# Sheet_1_2020-10-02_16-46-16.net
KiCad netlist of a schematic drawn in Altium Designer
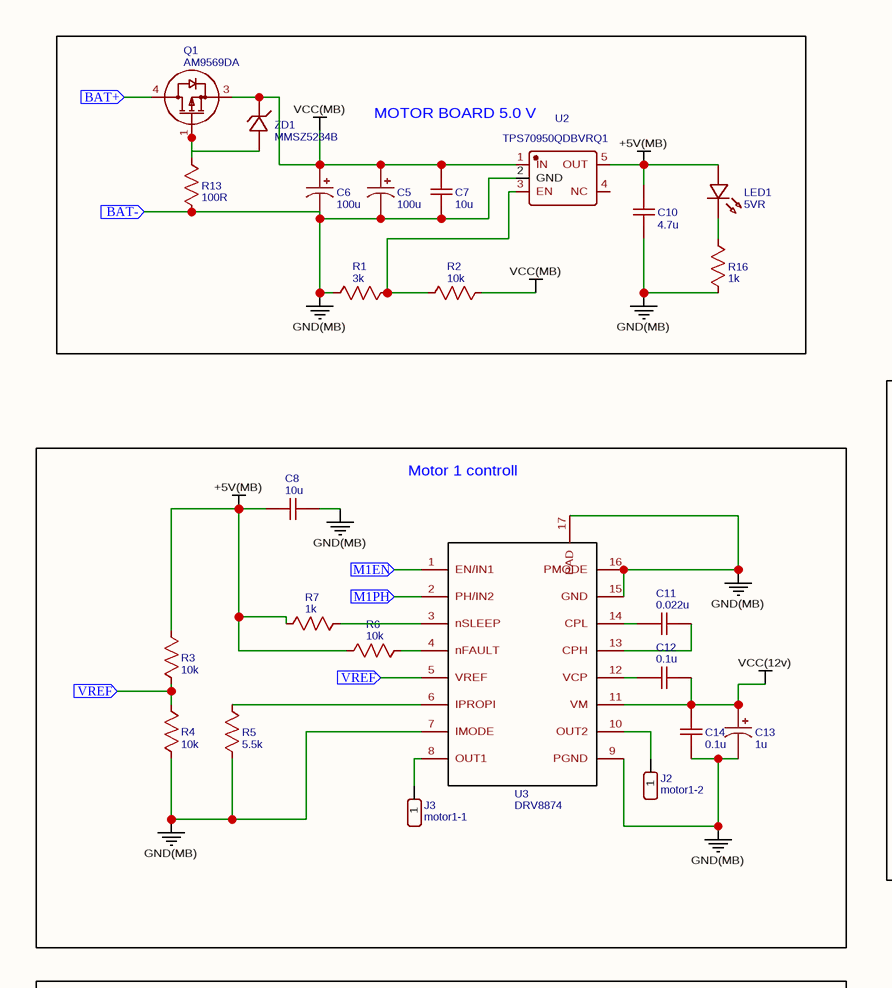
[diagram p0: Sheet_1_2020-10-02_16-46-16.schdoc, top left]
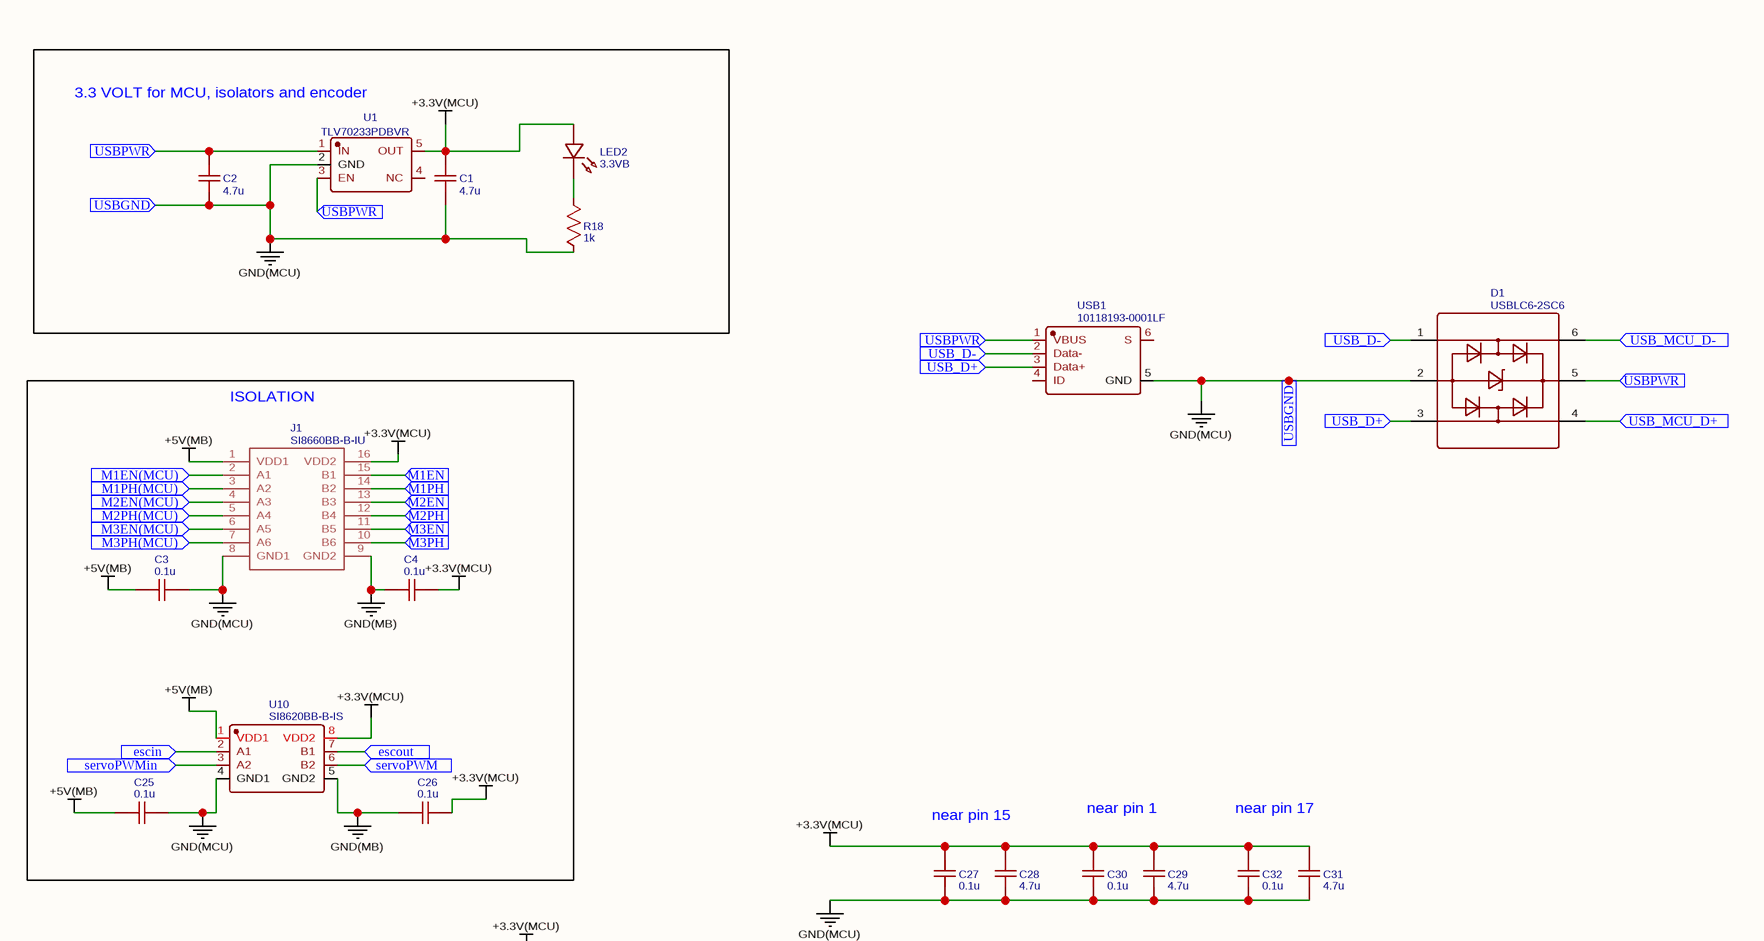
[diagram p1: Sheet_1_2020-10-02_16-46-16.schdoc, top right]
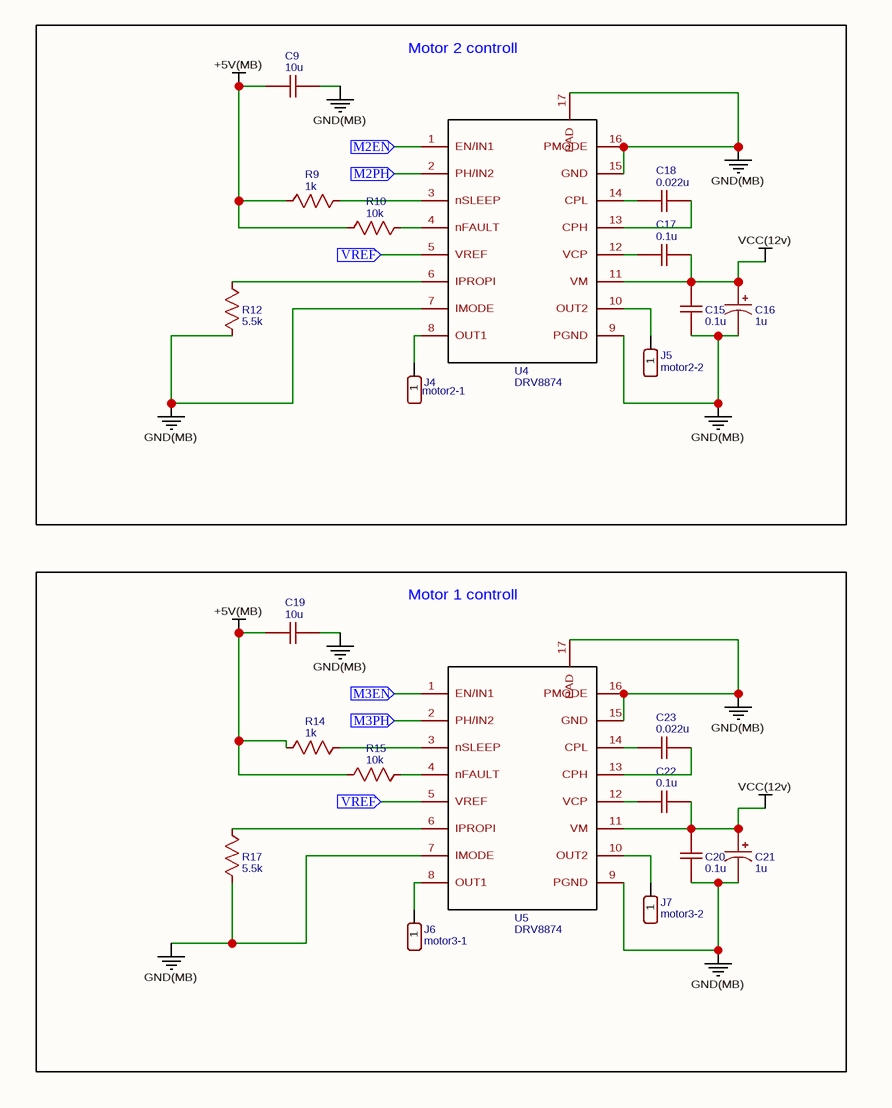
[diagram p2: Sheet_1_2020-10-02_16-46-16.schdoc, bottom left]
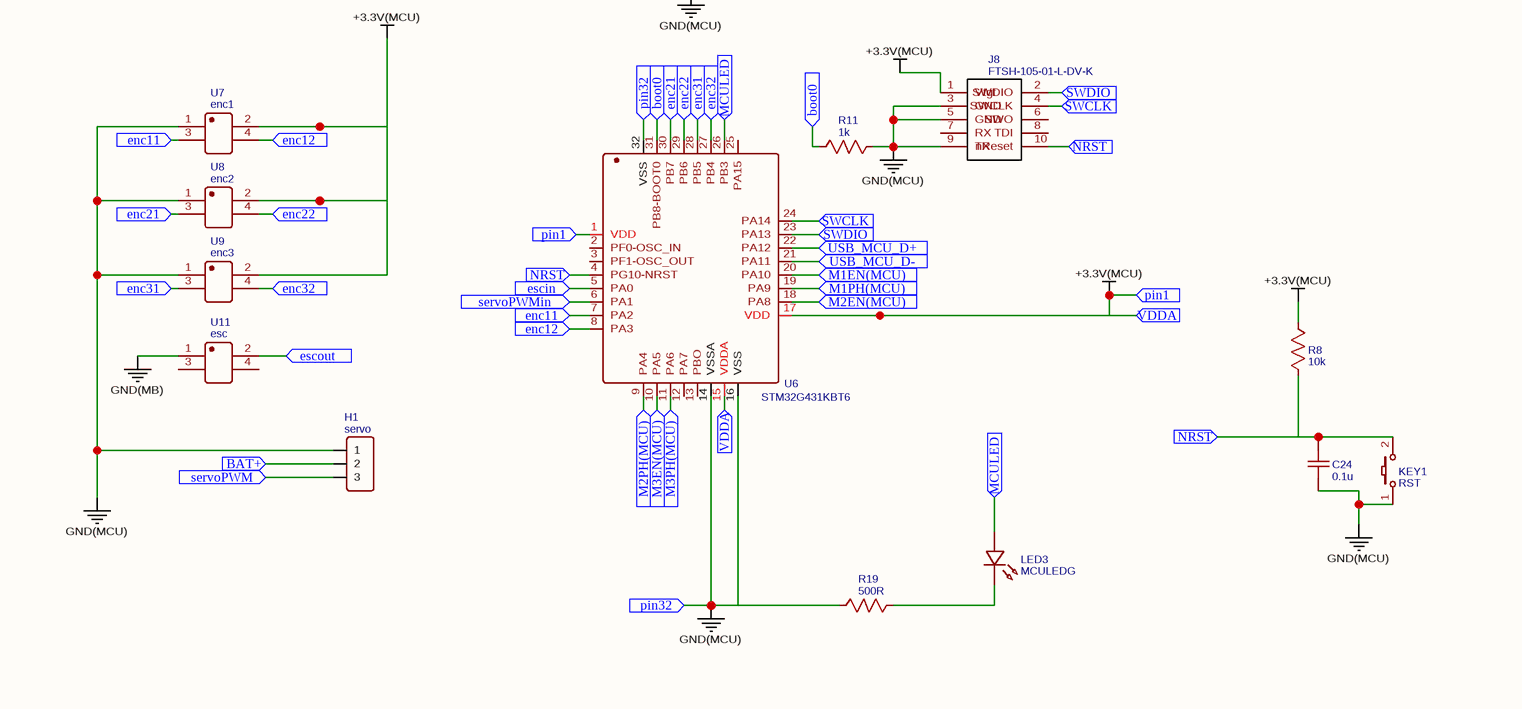
[diagram p3: Sheet_1_2020-10-02_16-46-16.schdoc, bottom right]

(export (version "E")
  (design (tool "Eeschema 10.0.6"))
  (components
    (comp (ref "C1")
      (value "4.7u")
      (fields (field (name "CONTRIBUTOR") "LCEDA_Lib"))
      (libsource (lib "altium-import") (part "root_1_4.7u_"))
    )
    (comp (ref "C2")
      (value "4.7u")
      (fields (field (name "CONTRIBUTOR") "LCEDA_Lib"))
      (libsource (lib "altium-import") (part "root_1_4.7u_"))
    )
    (comp (ref "C3")
      (value "0.1u")
      (fields (field (name "CONTRIBUTOR") "LCEDA_Lib"))
      (libsource (lib "altium-import") (part "root_2_0.1u_"))
    )
    (comp (ref "C4")
      (value "0.1u")
      (fields (field (name "CONTRIBUTOR") "LCEDA_Lib"))
      (libsource (lib "altium-import") (part "root_2_0.1u_"))
    )
    (comp (ref "C5")
      (value "100u")
      (fields (field (name "CONTRIBUTOR") "LCEDA_Lib"))
      (libsource (lib "altium-import") (part "root_3_100u_"))
    )
    (comp (ref "C6")
      (value "100u")
      (fields (field (name "CONTRIBUTOR") "LCEDA_Lib"))
      (libsource (lib "altium-import") (part "root_3_100u_"))
    )
    (comp (ref "C7")
      (value "10u")
      (fields (field (name "CONTRIBUTOR") "LCEDA_Lib"))
      (libsource (lib "altium-import") (part "root_1_10u_"))
    )
    (comp (ref "C8")
      (value "10u")
      (fields (field (name "CONTRIBUTOR") "LCEDA_Lib"))
      (libsource (lib "altium-import") (part "root_0_10u_"))
    )
    (comp (ref "C9")
      (value "10u")
      (fields (field (name "CONTRIBUTOR") "LCEDA_Lib"))
      (libsource (lib "altium-import") (part "root_0_10u_"))
    )
    (comp (ref "C10")
      (value "4.7u")
      (fields (field (name "CONTRIBUTOR") "LCEDA_Lib"))
      (libsource (lib "altium-import") (part "root_1_4.7u_"))
    )
    (comp (ref "C11")
      (value "0.022u")
      (fields (field (name "CONTRIBUTOR") "LCEDA_Lib"))
      (libsource (lib "altium-import") (part "root_0_0.022u_"))
    )
    (comp (ref "C12")
      (value "0.1u")
      (fields (field (name "CONTRIBUTOR") "LCEDA_Lib"))
      (libsource (lib "altium-import") (part "root_0_0.1u_"))
    )
    (comp (ref "C13")
      (value "1u")
      (fields (field (name "CONTRIBUTOR") "LCEDA_Lib"))
      (libsource (lib "altium-import") (part "root_3_1u_"))
    )
    (comp (ref "C14")
      (value "0.1u")
      (fields (field (name "CONTRIBUTOR") "LCEDA_Lib"))
      (libsource (lib "altium-import") (part "root_1_0.1u_"))
    )
    (comp (ref "C15")
      (value "0.1u")
      (fields (field (name "CONTRIBUTOR") "LCEDA_Lib"))
      (libsource (lib "altium-import") (part "root_1_0.1u_"))
    )
    (comp (ref "C16")
      (value "1u")
      (fields (field (name "CONTRIBUTOR") "LCEDA_Lib"))
      (libsource (lib "altium-import") (part "root_3_1u_"))
    )
    (comp (ref "C17")
      (value "0.1u")
      (fields (field (name "CONTRIBUTOR") "LCEDA_Lib"))
      (libsource (lib "altium-import") (part "root_0_0.1u_"))
    )
    (comp (ref "C18")
      (value "0.022u")
      (fields (field (name "CONTRIBUTOR") "LCEDA_Lib"))
      (libsource (lib "altium-import") (part "root_0_0.022u_"))
    )
    (comp (ref "C19")
      (value "10u")
      (fields (field (name "CONTRIBUTOR") "LCEDA_Lib"))
      (libsource (lib "altium-import") (part "root_0_10u_"))
    )
    (comp (ref "C20")
      (value "0.1u")
      (fields (field (name "CONTRIBUTOR") "LCEDA_Lib"))
      (libsource (lib "altium-import") (part "root_1_0.1u_"))
    )
    (comp (ref "C21")
      (value "1u")
      (fields (field (name "CONTRIBUTOR") "LCEDA_Lib"))
      (libsource (lib "altium-import") (part "root_3_1u_"))
    )
    (comp (ref "C22")
      (value "0.1u")
      (fields (field (name "CONTRIBUTOR") "LCEDA_Lib"))
      (libsource (lib "altium-import") (part "root_0_0.1u_"))
    )
    (comp (ref "C23")
      (value "0.022u")
      (fields (field (name "CONTRIBUTOR") "LCEDA_Lib"))
      (libsource (lib "altium-import") (part "root_0_0.022u_"))
    )
    (comp (ref "C24")
      (value "0.1u")
      (fields (field (name "CONTRIBUTOR") "LCEDA_Lib"))
      (libsource (lib "altium-import") (part "root_1_0.1u_"))
    )
    (comp (ref "C25")
      (value "0.1u")
      (fields (field (name "CONTRIBUTOR") "LCEDA_Lib"))
      (libsource (lib "altium-import") (part "root_2_0.1u_"))
    )
    (comp (ref "C26")
      (value "0.1u")
      (fields (field (name "CONTRIBUTOR") "LCEDA_Lib"))
      (libsource (lib "altium-import") (part "root_2_0.1u_"))
    )
    (comp (ref "C27")
      (value "0.1u")
      (fields (field (name "CONTRIBUTOR") "LCEDA_Lib"))
      (libsource (lib "altium-import") (part "root_1_0.1u_"))
    )
    (comp (ref "C28")
      (value "4.7u")
      (fields (field (name "CONTRIBUTOR") "LCEDA_Lib"))
      (libsource (lib "altium-import") (part "root_1_4.7u_"))
    )
    (comp (ref "C29")
      (value "4.7u")
      (fields (field (name "CONTRIBUTOR") "LCEDA_Lib"))
      (libsource (lib "altium-import") (part "root_1_4.7u_"))
    )
    (comp (ref "C30")
      (value "0.1u")
      (fields (field (name "CONTRIBUTOR") "LCEDA_Lib"))
      (libsource (lib "altium-import") (part "root_1_0.1u_"))
    )
    (comp (ref "C31")
      (value "4.7u")
      (fields (field (name "CONTRIBUTOR") "LCEDA_Lib"))
      (libsource (lib "altium-import") (part "root_1_4.7u_"))
    )
    (comp (ref "C32")
      (value "0.1u")
      (fields (field (name "CONTRIBUTOR") "LCEDA_Lib"))
      (libsource (lib "altium-import") (part "root_1_0.1u_"))
    )
    (comp (ref "D1")
      (value "USBLC6-2SC6")
      (fields (field (name "BOM_SUPPLIER PART") "C7519"))
      (libsource (lib "altium-import") (part "root_0_USBLC6-2SC6_"))
    )
    (comp (ref "H1")
      (value "servo")
      (fields (field (name "BOM_SUPPLIER PART") "C146690") (field (name "CONTRIBUTOR") "LCEDA_Lib"))
      (libsource (lib "altium-import") (part "root_0_servo_"))
    )
    (comp (ref "J1")
      (value "SI8660BB-B-IU")
      (fields (field (name "CONTRIBUTOR") "david rizhinashvili"))
      (libsource (lib "altium-import") (part "root_0_SI8660BB-B-IU_"))
    )
    (comp (ref "J2")
      (value "motor1-2")
      (fields (field (name "BOM_SUPPLIER PART") "C81276") (field (name "CONTRIBUTOR") "LCEDA_Lib"))
      (libsource (lib "altium-import") (part "root_3_motor1-2_"))
    )
    (comp (ref "J3")
      (value "motor1-1")
      (fields (field (name "BOM_SUPPLIER PART") "C81276") (field (name "CONTRIBUTOR") "LCEDA_Lib"))
      (libsource (lib "altium-import") (part "root_3_motor1-1_"))
    )
    (comp (ref "J4")
      (value "motor2-1")
      (fields (field (name "BOM_SUPPLIER PART") "C81276") (field (name "CONTRIBUTOR") "LCEDA_Lib"))
      (libsource (lib "altium-import") (part "root_3_motor2-1_"))
    )
    (comp (ref "J5")
      (value "motor2-2")
      (fields (field (name "BOM_SUPPLIER PART") "C81276") (field (name "CONTRIBUTOR") "LCEDA_Lib"))
      (libsource (lib "altium-import") (part "root_3_motor2-2_"))
    )
    (comp (ref "J6")
      (value "motor3-1")
      (fields (field (name "BOM_SUPPLIER PART") "C81276") (field (name "CONTRIBUTOR") "LCEDA_Lib"))
      (libsource (lib "altium-import") (part "root_3_motor3-1_"))
    )
    (comp (ref "J7")
      (value "motor3-2")
      (fields (field (name "BOM_SUPPLIER PART") "C81276") (field (name "CONTRIBUTOR") "LCEDA_Lib"))
      (libsource (lib "altium-import") (part "root_3_motor3-2_"))
    )
    (comp (ref "J8")
      (value "FTSH-105-01-L-DV-K")
      (fields (field (name "BOM_SUPPLIER PART") "SAM8799-ND") (field (name "CONTRIBUTOR") "OBC Gang"))
      (libsource (lib "altium-import") (part "root_0_FTSH-105-01-L-DV-K_"))
    )
    (comp (ref "KEY1")
      (value "RST")
      (fields
        (field (name "BOM_SUPPLIER PART") "C118141")
        (field (name "BOM_MANUFACTURER PART") "K2-1107ST-A4SW-06")
        (field (name "CONTRIBUTOR") "LCEDA_Lib")
      )
      (libsource (lib "altium-import") (part "root_1_RST_"))
    )
    (comp (ref "LED1")
      (value "5VR")
      (fields
        (field (name "BOM_MANUFACTURER PART") "19-217/R6C-AL1M2VY/3T")
        (field (name "BOM_SUPPLIER PART") "C72044")
        (field (name "CONTRIBUTOR") "LCEDA_01")
      )
      (libsource (lib "altium-import") (part "root_3_5VR_"))
    )
    (comp (ref "LED2")
      (value "3.3VB")
      (fields
        (field (name "BOM_MANUFACTURER PART") "19-217/R6C-AL1M2VY/3T")
        (field (name "BOM_SUPPLIER PART") "C72044")
        (field (name "CONTRIBUTOR") "LCEDA_01")
      )
      (libsource (lib "altium-import") (part "root_3_3.3VB_"))
    )
    (comp (ref "LED3")
      (value "MCULEDG")
      (fields
        (field (name "BOM_MANUFACTURER PART") "19-217/R6C-AL1M2VY/3T")
        (field (name "BOM_SUPPLIER PART") "C72044")
        (field (name "CONTRIBUTOR") "LCEDA_01")
      )
      (libsource (lib "altium-import") (part "root_3_MCULEDG_"))
    )
    (comp (ref "Q1")
      (value "AM9569DA")
      (fields (field (name "BOM_SUPPLIER PART") "C224223") (field (name "CONTRIBUTOR") "LCSC"))
      (libsource (lib "altium-import") (part "root_1_AM9569DA_"))
    )
    (comp (ref "R1")
      (value "3k")
      (fields (field (name "CONTRIBUTOR") "LCEDA_Lib"))
      (libsource (lib "altium-import") (part "root_0_3k_"))
    )
    (comp (ref "R2")
      (value "10k")
      (fields (field (name "CONTRIBUTOR") "LCEDA_Lib"))
      (libsource (lib "altium-import") (part "root_0_10k_"))
    )
    (comp (ref "R3")
      (value "10k")
      (fields (field (name "CONTRIBUTOR") "LCEDA_Lib"))
      (libsource (lib "altium-import") (part "root_3_10k_"))
    )
    (comp (ref "R4")
      (value "10k")
      (fields (field (name "CONTRIBUTOR") "LCEDA_Lib"))
      (libsource (lib "altium-import") (part "root_3_10k_"))
    )
    (comp (ref "R5")
      (value "5.5k")
      (fields (field (name "CONTRIBUTOR") "LCEDA_Lib"))
      (libsource (lib "altium-import") (part "root_1_5.5k_"))
    )
    (comp (ref "R6")
      (value "10k")
      (fields (field (name "CONTRIBUTOR") "LCEDA_Lib"))
      (libsource (lib "altium-import") (part "root_0_10k_"))
    )
    (comp (ref "R7")
      (value "1k")
      (fields (field (name "CONTRIBUTOR") "LCEDA_Lib"))
      (libsource (lib "altium-import") (part "root_0_1k_"))
    )
    (comp (ref "R8")
      (value "10k")
      (fields (field (name "CONTRIBUTOR") "LCEDA_Lib"))
      (libsource (lib "altium-import") (part "root_1_10k_"))
    )
    (comp (ref "R9")
      (value "1k")
      (fields (field (name "CONTRIBUTOR") "LCEDA_Lib"))
      (libsource (lib "altium-import") (part "root_0_1k_"))
    )
    (comp (ref "R10")
      (value "10k")
      (fields (field (name "CONTRIBUTOR") "LCEDA_Lib"))
      (libsource (lib "altium-import") (part "root_0_10k_"))
    )
    (comp (ref "R11")
      (value "1k")
      (fields (field (name "CONTRIBUTOR") "LCEDA_Lib"))
      (libsource (lib "altium-import") (part "root_0_1k_"))
    )
    (comp (ref "R12")
      (value "5.5k")
      (fields (field (name "CONTRIBUTOR") "LCEDA_Lib"))
      (libsource (lib "altium-import") (part "root_1_5.5k_"))
    )
    (comp (ref "R13")
      (value "100R")
      (fields (field (name "CONTRIBUTOR") "LCEDA_Lib"))
      (libsource (lib "altium-import") (part "root_1_100R_"))
    )
    (comp (ref "R14")
      (value "1k")
      (fields (field (name "CONTRIBUTOR") "LCEDA_Lib"))
      (libsource (lib "altium-import") (part "root_0_1k_"))
    )
    (comp (ref "R15")
      (value "10k")
      (fields (field (name "CONTRIBUTOR") "LCEDA_Lib"))
      (libsource (lib "altium-import") (part "root_0_10k_"))
    )
    (comp (ref "R16")
      (value "1k")
      (fields (field (name "CONTRIBUTOR") "LCEDA_Lib"))
      (libsource (lib "altium-import") (part "root_1_1k_"))
    )
    (comp (ref "R17")
      (value "5.5k")
      (fields (field (name "CONTRIBUTOR") "LCEDA_Lib"))
      (libsource (lib "altium-import") (part "root_1_5.5k_"))
    )
    (comp (ref "R18")
      (value "1k")
      (fields (field (name "CONTRIBUTOR") "LCEDA_Lib"))
      (libsource (lib "altium-import") (part "root_1_1k_"))
    )
    (comp (ref "R19")
      (value "500R")
      (fields (field (name "CONTRIBUTOR") "LCEDA_Lib"))
      (libsource (lib "altium-import") (part "root_0_500R_"))
    )
    (comp (ref "U1")
      (value "TLV70233PDBVR")
      (fields (field (name "BOM_SUPPLIER PART") "C123134") (field (name "CONTRIBUTOR") "LCSC"))
      (libsource (lib "altium-import") (part "root_0_TLV70233PDBVR_"))
    )
    (comp (ref "U2")
      (value "TPS70950QDBVRQ1")
      (fields (field (name "BOM_SUPPLIER PART") "C485909") (field (name "CONTRIBUTOR") "LCSC"))
      (libsource (lib "altium-import") (part "root_0_TPS70950QDBVRQ1_"))
    )
    (comp (ref "U3")
      (value "DRV8874")
      (fields (field (name "CONTRIBUTOR") "Plexus"))
      (libsource (lib "altium-import") (part "root_0_DRV8874_"))
    )
    (comp (ref "U4")
      (value "DRV8874")
      (fields (field (name "CONTRIBUTOR") "Plexus"))
      (libsource (lib "altium-import") (part "root_0_DRV8874_"))
    )
    (comp (ref "U5")
      (value "DRV8874")
      (fields (field (name "CONTRIBUTOR") "Plexus"))
      (libsource (lib "altium-import") (part "root_0_DRV8874_"))
    )
    (comp (ref "U6")
      (value "STM32G431KBT6")
      (fields (field (name "BOM_SUPPLIER PART") "C529357") (field (name "CONTRIBUTOR") "LCSC"))
      (libsource (lib "altium-import") (part "root_0_STM32G431KBT6_"))
    )
    (comp (ref "U7")
      (value "enc1")
      (fields
        (field (name "BOM_SUPPLIER PART") "C306232")
        (field (name "BOM_MANUFACTURER PART") "215079-4")
        (field (name "CONTRIBUTOR") "LCSC")
      )
      (libsource (lib "altium-import") (part "root_0_enc1_"))
    )
    (comp (ref "U8")
      (value "enc2")
      (fields
        (field (name "BOM_SUPPLIER PART") "C306232")
        (field (name "BOM_MANUFACTURER PART") "215079-4")
        (field (name "CONTRIBUTOR") "LCSC")
      )
      (libsource (lib "altium-import") (part "root_0_enc2_"))
    )
    (comp (ref "U9")
      (value "enc3")
      (fields
        (field (name "BOM_SUPPLIER PART") "C306232")
        (field (name "BOM_MANUFACTURER PART") "215079-4")
        (field (name "CONTRIBUTOR") "LCSC")
      )
      (libsource (lib "altium-import") (part "root_0_enc3_"))
    )
    (comp (ref "U10")
      (value "SI8620BB-B-IS")
      (fields (field (name "BOM_SUPPLIER PART") "C430264") (field (name "CONTRIBUTOR") "LCSC"))
      (libsource (lib "altium-import") (part "root_0_SI8620BB-B-IS_"))
    )
    (comp (ref "U11")
      (value "esc")
      (fields
        (field (name "BOM_SUPPLIER PART") "C306232")
        (field (name "BOM_MANUFACTURER PART") "215079-4")
        (field (name "CONTRIBUTOR") "LCSC")
      )
      (libsource (lib "altium-import") (part "root_0_esc_"))
    )
    (comp (ref "USB1")
      (value "10118193-0001LF")
      (fields (field (name "BOM_SUPPLIER PART") "C132562") (field (name "CONTRIBUTOR") "LCSC"))
      (libsource (lib "altium-import") (part "root_0_10118193-0001LF_"))
    )
    (comp (ref "ZD1")
      (value "MMSZ5234B")
      (fields (field (name "BOM_SUPPLIER PART") "C21556"))
      (libsource (lib "altium-import") (part "root_3_MMSZ5234B_"))
    )
  )
  (nets
    (net (code "1") (name "+3.3V(MCU)") (class "Default")
      (node (ref "C1") (pin "2") (pinfunction "2_2") (pintype "passive"))
      (node (ref "C26") (pin "1") (pinfunction "1_1") (pintype "passive"))
      (node (ref "C27") (pin "2") (pinfunction "2_2") (pintype "passive"))
      (node (ref "C28") (pin "2") (pinfunction "2_2") (pintype "passive"))
      (node (ref "C29") (pin "2") (pinfunction "2_2") (pintype "passive"))
      (node (ref "C30") (pin "2") (pinfunction "2_2") (pintype "passive"))
      (node (ref "C31") (pin "2") (pinfunction "2_2") (pintype "passive"))
      (node (ref "C32") (pin "2") (pinfunction "2_2") (pintype "passive"))
      (node (ref "C4") (pin "1") (pinfunction "1_1") (pintype "passive"))
      (node (ref "J1") (pin "16") (pinfunction "VDD2_16") (pintype "passive"))
      (node (ref "J8") (pin "1") (pinfunction "Vtgt_1") (pintype "passive"))
      (node (ref "LED2") (pin "1") (pinfunction "1_1") (pintype "passive"))
      (node (ref "R8") (pin "2") (pinfunction "2_2") (pintype "passive"))
      (node (ref "U1") (pin "5") (pinfunction "OUT_5") (pintype "passive"))
      (node (ref "U10") (pin "8") (pinfunction "VDD2_8") (pintype "passive"))
      (node (ref "U6") (pin "1") (pinfunction "VDD_1") (pintype "passive"))
      (node (ref "U6") (pin "15") (pinfunction "VDDA_15") (pintype "passive"))
      (node (ref "U6") (pin "17") (pinfunction "VDD_17") (pintype "passive"))
      (node (ref "U7") (pin "2") (pinfunction "2_2") (pintype "passive"))
      (node (ref "U8") (pin "2") (pinfunction "2_2") (pintype "passive"))
      (node (ref "U9") (pin "2") (pinfunction "2_2") (pintype "passive"))
    )
    (net (code "2") (name "+5V(MB)") (class "Default")
      (node (ref "C10") (pin "2") (pinfunction "2_2") (pintype "passive"))
      (node (ref "C19") (pin "1") (pinfunction "1_1") (pintype "passive"))
      (node (ref "C25") (pin "2") (pinfunction "2_2") (pintype "passive"))
      (node (ref "C3") (pin "2") (pinfunction "2_2") (pintype "passive"))
      (node (ref "C8") (pin "1") (pinfunction "1_1") (pintype "passive"))
      (node (ref "C9") (pin "1") (pinfunction "1_1") (pintype "passive"))
      (node (ref "J1") (pin "1") (pinfunction "VDD1_1") (pintype "passive"))
      (node (ref "LED1") (pin "1") (pinfunction "1_1") (pintype "passive"))
      (node (ref "R10") (pin "1") (pinfunction "1_1") (pintype "passive"))
      (node (ref "R14") (pin "1") (pinfunction "1_1") (pintype "passive"))
      (node (ref "R15") (pin "1") (pinfunction "1_1") (pintype "passive"))
      (node (ref "R3") (pin "1") (pinfunction "1_1") (pintype "passive"))
      (node (ref "R6") (pin "1") (pinfunction "1_1") (pintype "passive"))
      (node (ref "R7") (pin "1") (pinfunction "1_1") (pintype "passive"))
      (node (ref "R9") (pin "1") (pinfunction "1_1") (pintype "passive"))
      (node (ref "U10") (pin "1") (pinfunction "VDD1_1") (pintype "passive"))
      (node (ref "U2") (pin "5") (pinfunction "OUT_5") (pintype "passive"))
    )
    (net (code "3") (name "/BAT+") (class "Default")
      (node (ref "H1") (pin "2") (pinfunction "2_2") (pintype "passive"))
      (node (ref "Q1") (pin "4") (pinfunction "D_4") (pintype "passive"))
    )
    (net (code "4") (name "/M1EN") (class "Default")
      (node (ref "J1") (pin "15") (pinfunction "B1_15") (pintype "passive"))
      (node (ref "U3") (pin "1") (pinfunction "EN/IN1_1") (pintype "passive"))
    )
    (net (code "5") (name "/M1EN(MCU)") (class "Default")
      (node (ref "J1") (pin "2") (pinfunction "A1_2") (pintype "passive"))
      (node (ref "U6") (pin "20") (pinfunction "PA10_20") (pintype "passive"))
    )
    (net (code "6") (name "/M1PH") (class "Default")
      (node (ref "J1") (pin "14") (pinfunction "B2_14") (pintype "passive"))
      (node (ref "U3") (pin "2") (pinfunction "PH/IN2_2") (pintype "passive"))
    )
    (net (code "7") (name "/M1PH(MCU)") (class "Default")
      (node (ref "J1") (pin "3") (pinfunction "A2_3") (pintype "passive"))
      (node (ref "U6") (pin "19") (pinfunction "PA9_19") (pintype "passive"))
    )
    (net (code "8") (name "/M2EN") (class "Default")
      (node (ref "J1") (pin "13") (pinfunction "B3_13") (pintype "passive"))
      (node (ref "U4") (pin "1") (pinfunction "EN/IN1_1") (pintype "passive"))
    )
    (net (code "9") (name "/M2EN(MCU)") (class "Default")
      (node (ref "J1") (pin "4") (pinfunction "A3_4") (pintype "passive"))
      (node (ref "U6") (pin "18") (pinfunction "PA8_18") (pintype "passive"))
    )
    (net (code "10") (name "/M2PH") (class "Default")
      (node (ref "J1") (pin "12") (pinfunction "B4_12") (pintype "passive"))
      (node (ref "U4") (pin "2") (pinfunction "PH/IN2_2") (pintype "passive"))
    )
    (net (code "11") (name "/M2PH(MCU)") (class "Default")
      (node (ref "J1") (pin "5") (pinfunction "A4_5") (pintype "passive"))
      (node (ref "U6") (pin "9") (pinfunction "PA4_9") (pintype "passive"))
    )
    (net (code "12") (name "/M3EN") (class "Default")
      (node (ref "J1") (pin "11") (pinfunction "B5_11") (pintype "passive"))
      (node (ref "U5") (pin "1") (pinfunction "EN/IN1_1") (pintype "passive"))
    )
    (net (code "13") (name "/M3EN(MCU)") (class "Default")
      (node (ref "J1") (pin "6") (pinfunction "A5_6") (pintype "passive"))
      (node (ref "U6") (pin "10") (pinfunction "PA5_10") (pintype "passive"))
    )
    (net (code "14") (name "/M3PH") (class "Default")
      (node (ref "J1") (pin "10") (pinfunction "B6_10") (pintype "passive"))
      (node (ref "U5") (pin "2") (pinfunction "PH/IN2_2") (pintype "passive"))
    )
    (net (code "15") (name "/M3PH(MCU)") (class "Default")
      (node (ref "J1") (pin "7") (pinfunction "A6_7") (pintype "passive"))
      (node (ref "U6") (pin "11") (pinfunction "PA6_11") (pintype "passive"))
    )
    (net (code "16") (name "/MCULED") (class "Default")
      (node (ref "LED3") (pin "1") (pinfunction "1_1") (pintype "passive"))
      (node (ref "U6") (pin "26") (pinfunction "PB3_26") (pintype "passive"))
    )
    (net (code "17") (name "/NRST") (class "Default")
      (node (ref "C24") (pin "2") (pinfunction "2_2") (pintype "passive"))
      (node (ref "J8") (pin "10") (pinfunction "nReset_10") (pintype "passive"))
      (node (ref "KEY1") (pin "2") (pinfunction "2_2") (pintype "passive"))
      (node (ref "R8") (pin "1") (pinfunction "1_1") (pintype "passive"))
      (node (ref "U6") (pin "4") (pinfunction "PG10-NRST_4") (pintype "passive"))
    )
    (net (code "18") (name "/SWCLK") (class "Default")
      (node (ref "J8") (pin "4") (pinfunction "SWCLK_4") (pintype "passive"))
      (node (ref "U6") (pin "24") (pinfunction "PA14_24") (pintype "passive"))
    )
    (net (code "19") (name "/SWDIO") (class "Default")
      (node (ref "J8") (pin "2") (pinfunction "SWDIO_2") (pintype "passive"))
      (node (ref "U6") (pin "23") (pinfunction "PA13_23") (pintype "passive"))
    )
    (net (code "20") (name "/USBPWR") (class "Default")
      (node (ref "C2") (pin "2") (pinfunction "2_2") (pintype "passive"))
      (node (ref "D1") (pin "5") (pinfunction "5_5") (pintype "passive"))
      (node (ref "U1") (pin "1") (pinfunction "IN_1") (pintype "passive"))
      (node (ref "U1") (pin "3") (pinfunction "EN_3") (pintype "passive"))
      (node (ref "USB1") (pin "1") (pinfunction "VBUS_1") (pintype "passive"))
    )
    (net (code "21") (name "/USB_D+") (class "Default")
      (node (ref "D1") (pin "3") (pinfunction "3_3") (pintype "passive"))
      (node (ref "USB1") (pin "3") (pinfunction "Data+_3") (pintype "passive"))
    )
    (net (code "22") (name "/USB_D-") (class "Default")
      (node (ref "D1") (pin "1") (pinfunction "1_1") (pintype "passive"))
      (node (ref "USB1") (pin "2") (pinfunction "Data-_2") (pintype "passive"))
    )
    (net (code "23") (name "/USB_MCU_D+") (class "Default")
      (node (ref "D1") (pin "4") (pinfunction "4_4") (pintype "passive"))
      (node (ref "U6") (pin "22") (pinfunction "PA12_22") (pintype "passive"))
    )
    (net (code "24") (name "/USB_MCU_D-") (class "Default")
      (node (ref "D1") (pin "6") (pinfunction "6_6") (pintype "passive"))
      (node (ref "U6") (pin "21") (pinfunction "PA11_21") (pintype "passive"))
    )
    (net (code "25") (name "/VREF") (class "Default")
      (node (ref "R3") (pin "2") (pinfunction "2_2") (pintype "passive"))
      (node (ref "R4") (pin "1") (pinfunction "1_1") (pintype "passive"))
      (node (ref "U3") (pin "5") (pinfunction "VREF_5") (pintype "passive"))
      (node (ref "U4") (pin "5") (pinfunction "VREF_5") (pintype "passive"))
      (node (ref "U5") (pin "5") (pinfunction "VREF_5") (pintype "passive"))
    )
    (net (code "26") (name "/boot0") (class "Default")
      (node (ref "R11") (pin "1") (pinfunction "1_1") (pintype "passive"))
      (node (ref "U6") (pin "31") (pinfunction "PB8-BOOT0_31") (pintype "passive"))
    )
    (net (code "27") (name "/enc11") (class "Default")
      (node (ref "U6") (pin "7") (pinfunction "PA2_7") (pintype "passive"))
      (node (ref "U7") (pin "3") (pinfunction "3_3") (pintype "passive"))
    )
    (net (code "28") (name "/enc12") (class "Default")
      (node (ref "U6") (pin "8") (pinfunction "PA3_8") (pintype "passive"))
      (node (ref "U7") (pin "4") (pinfunction "4_4") (pintype "passive"))
    )
    (net (code "29") (name "/enc21") (class "Default")
      (node (ref "U6") (pin "30") (pinfunction "PB7_30") (pintype "passive"))
      (node (ref "U8") (pin "3") (pinfunction "3_3") (pintype "passive"))
    )
    (net (code "30") (name "/enc22") (class "Default")
      (node (ref "U6") (pin "29") (pinfunction "PB6_29") (pintype "passive"))
      (node (ref "U8") (pin "4") (pinfunction "4_4") (pintype "passive"))
    )
    (net (code "31") (name "/enc31") (class "Default")
      (node (ref "U6") (pin "28") (pinfunction "PB5_28") (pintype "passive"))
      (node (ref "U9") (pin "3") (pinfunction "3_3") (pintype "passive"))
    )
    (net (code "32") (name "/enc32") (class "Default")
      (node (ref "U6") (pin "27") (pinfunction "PB4_27") (pintype "passive"))
      (node (ref "U9") (pin "4") (pinfunction "4_4") (pintype "passive"))
    )
    (net (code "33") (name "/escin") (class "Default")
      (node (ref "U10") (pin "2") (pinfunction "A1_2") (pintype "passive"))
      (node (ref "U6") (pin "5") (pinfunction "PA0_5") (pintype "passive"))
    )
    (net (code "34") (name "/escout") (class "Default")
      (node (ref "U10") (pin "7") (pinfunction "B1_7") (pintype "passive"))
      (node (ref "U11") (pin "2") (pinfunction "2_2") (pintype "passive"))
    )
    (net (code "35") (name "/servoPWM") (class "Default")
      (node (ref "H1") (pin "3") (pinfunction "3_3") (pintype "passive"))
      (node (ref "U10") (pin "6") (pinfunction "B2_6") (pintype "passive"))
    )
    (net (code "36") (name "/servoPWMin") (class "Default")
      (node (ref "U10") (pin "3") (pinfunction "A2_3") (pintype "passive"))
      (node (ref "U6") (pin "6") (pinfunction "PA1_6") (pintype "passive"))
    )
    (net (code "37") (name "GND(MB)") (class "Default")
      (node (ref "C10") (pin "1") (pinfunction "1_1") (pintype "passive"))
      (node (ref "C13") (pin "2") (pinfunction "2_2") (pintype "passive"))
      (node (ref "C14") (pin "1") (pinfunction "1_1") (pintype "passive"))
      (node (ref "C15") (pin "1") (pinfunction "1_1") (pintype "passive"))
      (node (ref "C16") (pin "2") (pinfunction "2_2") (pintype "passive"))
      (node (ref "C19") (pin "2") (pinfunction "2_2") (pintype "passive"))
      (node (ref "C20") (pin "1") (pinfunction "1_1") (pintype "passive"))
      (node (ref "C21") (pin "2") (pinfunction "2_2") (pintype "passive"))
      (node (ref "C26") (pin "2") (pinfunction "2_2") (pintype "passive"))
      (node (ref "C4") (pin "2") (pinfunction "2_2") (pintype "passive"))
      (node (ref "C5") (pin "2") (pinfunction "2_2") (pintype "passive"))
      (node (ref "C6") (pin "2") (pinfunction "2_2") (pintype "passive"))
      (node (ref "C7") (pin "1") (pinfunction "1_1") (pintype "passive"))
      (node (ref "C8") (pin "2") (pinfunction "2_2") (pintype "passive"))
      (node (ref "C9") (pin "2") (pinfunction "2_2") (pintype "passive"))
      (node (ref "J1") (pin "9") (pinfunction "GND2_9") (pintype "passive"))
      (node (ref "R1") (pin "1") (pinfunction "1_1") (pintype "passive"))
      (node (ref "R12") (pin "1") (pinfunction "1_1") (pintype "passive"))
      (node (ref "R13") (pin "1") (pinfunction "1_1") (pintype "passive"))
      (node (ref "R16") (pin "1") (pinfunction "1_1") (pintype "passive"))
      (node (ref "R17") (pin "1") (pinfunction "1_1") (pintype "passive"))
      (node (ref "R4") (pin "2") (pinfunction "2_2") (pintype "passive"))
      (node (ref "R5") (pin "1") (pinfunction "1_1") (pintype "passive"))
      (node (ref "U10") (pin "5") (pinfunction "GND2_5") (pintype "passive"))
      (node (ref "U11") (pin "1") (pinfunction "1_1") (pintype "passive"))
      (node (ref "U2") (pin "2") (pinfunction "GND_2") (pintype "passive"))
      (node (ref "U3") (pin "15") (pinfunction "GND_15") (pintype "passive"))
      (node (ref "U3") (pin "16") (pinfunction "PMODE_16") (pintype "passive"))
      (node (ref "U3") (pin "17") (pinfunction "PAD_17") (pintype "passive"))
      (node (ref "U3") (pin "7") (pinfunction "IMODE_7") (pintype "passive"))
      (node (ref "U3") (pin "9") (pinfunction "PGND_9") (pintype "passive"))
      (node (ref "U4") (pin "15") (pinfunction "GND_15") (pintype "passive"))
      (node (ref "U4") (pin "16") (pinfunction "PMODE_16") (pintype "passive"))
      (node (ref "U4") (pin "17") (pinfunction "PAD_17") (pintype "passive"))
      (node (ref "U4") (pin "7") (pinfunction "IMODE_7") (pintype "passive"))
      (node (ref "U4") (pin "9") (pinfunction "PGND_9") (pintype "passive"))
      (node (ref "U5") (pin "15") (pinfunction "GND_15") (pintype "passive"))
      (node (ref "U5") (pin "16") (pinfunction "PMODE_16") (pintype "passive"))
      (node (ref "U5") (pin "17") (pinfunction "PAD_17") (pintype "passive"))
      (node (ref "U5") (pin "7") (pinfunction "IMODE_7") (pintype "passive"))
      (node (ref "U5") (pin "9") (pinfunction "PGND_9") (pintype "passive"))
    )
    (net (code "38") (name "GND(MCU)") (class "Default")
      (node (ref "C1") (pin "1") (pinfunction "1_1") (pintype "passive"))
      (node (ref "C2") (pin "1") (pinfunction "1_1") (pintype "passive"))
      (node (ref "C24") (pin "1") (pinfunction "1_1") (pintype "passive"))
      (node (ref "C25") (pin "1") (pinfunction "1_1") (pintype "passive"))
      (node (ref "C27") (pin "1") (pinfunction "1_1") (pintype "passive"))
      (node (ref "C28") (pin "1") (pinfunction "1_1") (pintype "passive"))
      (node (ref "C29") (pin "1") (pinfunction "1_1") (pintype "passive"))
      (node (ref "C3") (pin "1") (pinfunction "1_1") (pintype "passive"))
      (node (ref "C30") (pin "1") (pinfunction "1_1") (pintype "passive"))
      (node (ref "C31") (pin "1") (pinfunction "1_1") (pintype "passive"))
      (node (ref "C32") (pin "1") (pinfunction "1_1") (pintype "passive"))
      (node (ref "D1") (pin "2") (pinfunction "2_2") (pintype "passive"))
      (node (ref "H1") (pin "1") (pinfunction "1_1") (pintype "passive"))
      (node (ref "J1") (pin "8") (pinfunction "GND1_8") (pintype "passive"))
      (node (ref "J8") (pin "3") (pinfunction "GND_3") (pintype "passive"))
      (node (ref "J8") (pin "5") (pinfunction "GND_5") (pintype "passive"))
      (node (ref "J8") (pin "9") (pinfunction "TX_9") (pintype "passive"))
      (node (ref "KEY1") (pin "1") (pinfunction "1_1") (pintype "passive"))
      (node (ref "R11") (pin "2") (pinfunction "2_2") (pintype "passive"))
      (node (ref "R18") (pin "1") (pinfunction "1_1") (pintype "passive"))
      (node (ref "R19") (pin "1") (pinfunction "1_1") (pintype "passive"))
      (node (ref "U1") (pin "2") (pinfunction "GND_2") (pintype "passive"))
      (node (ref "U10") (pin "4") (pinfunction "GND1_4") (pintype "passive"))
      (node (ref "U6") (pin "14") (pinfunction "VSSA_14") (pintype "passive"))
      (node (ref "U6") (pin "16") (pinfunction "VSS_16") (pintype "passive"))
      (node (ref "U6") (pin "32") (pinfunction "VSS_32") (pintype "passive"))
      (node (ref "U7") (pin "1") (pinfunction "1_1") (pintype "passive"))
      (node (ref "U8") (pin "1") (pinfunction "1_1") (pintype "passive"))
      (node (ref "U9") (pin "1") (pinfunction "1_1") (pintype "passive"))
      (node (ref "USB1") (pin "5") (pinfunction "GND_5") (pintype "passive"))
    )
    (net (code "39") (name "Net-(LED1-Pad2)") (class "Default")
      (node (ref "LED1") (pin "2") (pinfunction "2_2") (pintype "passive"))
      (node (ref "R16") (pin "2") (pinfunction "2_2") (pintype "passive"))
    )
    (net (code "40") (name "Net-(LED2-Pad2)") (class "Default")
      (node (ref "LED2") (pin "2") (pinfunction "2_2") (pintype "passive"))
      (node (ref "R18") (pin "2") (pinfunction "2_2") (pintype "passive"))
    )
    (net (code "41") (name "Net-(LED3-Pad2)") (class "Default")
      (node (ref "LED3") (pin "2") (pinfunction "2_2") (pintype "passive"))
      (node (ref "R19") (pin "2") (pinfunction "2_2") (pintype "passive"))
    )
    (net (code "42") (name "Net-(Q1-G)") (class "Default")
      (node (ref "Q1") (pin "1") (pinfunction "G_1") (pintype "passive"))
      (node (ref "R13") (pin "2") (pinfunction "2_2") (pintype "passive"))
      (node (ref "ZD1") (pin "2") (pinfunction "A_2") (pintype "passive"))
    )
    (net (code "43") (name "Net-(U2-EN)") (class "Default")
      (node (ref "R1") (pin "2") (pinfunction "2_2") (pintype "passive"))
      (node (ref "R2") (pin "1") (pinfunction "1_1") (pintype "passive"))
      (node (ref "U2") (pin "3") (pinfunction "EN_3") (pintype "passive"))
    )
    (net (code "44") (name "Net-(U3-CPH)") (class "Default")
      (node (ref "C11") (pin "2") (pinfunction "2_2") (pintype "passive"))
      (node (ref "U3") (pin "13") (pinfunction "CPH_13") (pintype "passive"))
    )
    (net (code "45") (name "Net-(U3-CPL)") (class "Default")
      (node (ref "C11") (pin "1") (pinfunction "1_1") (pintype "passive"))
      (node (ref "U3") (pin "14") (pinfunction "CPL_14") (pintype "passive"))
    )
    (net (code "46") (name "Net-(U3-IPROPI)") (class "Default")
      (node (ref "R5") (pin "2") (pinfunction "2_2") (pintype "passive"))
      (node (ref "U3") (pin "6") (pinfunction "IPROPI_6") (pintype "passive"))
    )
    (net (code "47") (name "Net-(U3-OUT1)") (class "Default")
      (node (ref "J3") (pin "1") (pinfunction "1_1") (pintype "passive"))
      (node (ref "U3") (pin "8") (pinfunction "OUT1_8") (pintype "passive"))
    )
    (net (code "48") (name "Net-(U3-OUT2)") (class "Default")
      (node (ref "J2") (pin "1") (pinfunction "1_1") (pintype "passive"))
      (node (ref "U3") (pin "10") (pinfunction "OUT2_10") (pintype "passive"))
    )
    (net (code "49") (name "Net-(U3-VCP)") (class "Default")
      (node (ref "C12") (pin "1") (pinfunction "1_1") (pintype "passive"))
      (node (ref "U3") (pin "12") (pinfunction "VCP_12") (pintype "passive"))
    )
    (net (code "50") (name "Net-(U3-nFAULT)") (class "Default")
      (node (ref "R6") (pin "2") (pinfunction "2_2") (pintype "passive"))
      (node (ref "U3") (pin "4") (pinfunction "nFAULT_4") (pintype "passive"))
    )
    (net (code "51") (name "Net-(U3-nSLEEP)") (class "Default")
      (node (ref "R7") (pin "2") (pinfunction "2_2") (pintype "passive"))
      (node (ref "U3") (pin "3") (pinfunction "nSLEEP_3") (pintype "passive"))
    )
    (net (code "52") (name "Net-(U4-CPH)") (class "Default")
      (node (ref "C18") (pin "2") (pinfunction "2_2") (pintype "passive"))
      (node (ref "U4") (pin "13") (pinfunction "CPH_13") (pintype "passive"))
    )
    (net (code "53") (name "Net-(U4-CPL)") (class "Default")
      (node (ref "C18") (pin "1") (pinfunction "1_1") (pintype "passive"))
      (node (ref "U4") (pin "14") (pinfunction "CPL_14") (pintype "passive"))
    )
    (net (code "54") (name "Net-(U4-IPROPI)") (class "Default")
      (node (ref "R12") (pin "2") (pinfunction "2_2") (pintype "passive"))
      (node (ref "U4") (pin "6") (pinfunction "IPROPI_6") (pintype "passive"))
    )
    (net (code "55") (name "Net-(U4-OUT1)") (class "Default")
      (node (ref "J4") (pin "1") (pinfunction "1_1") (pintype "passive"))
      (node (ref "U4") (pin "8") (pinfunction "OUT1_8") (pintype "passive"))
    )
    (net (code "56") (name "Net-(U4-OUT2)") (class "Default")
      (node (ref "J5") (pin "1") (pinfunction "1_1") (pintype "passive"))
      (node (ref "U4") (pin "10") (pinfunction "OUT2_10") (pintype "passive"))
    )
    (net (code "57") (name "Net-(U4-VCP)") (class "Default")
      (node (ref "C17") (pin "1") (pinfunction "1_1") (pintype "passive"))
      (node (ref "U4") (pin "12") (pinfunction "VCP_12") (pintype "passive"))
    )
    (net (code "58") (name "Net-(U4-nFAULT)") (class "Default")
      (node (ref "R10") (pin "2") (pinfunction "2_2") (pintype "passive"))
      (node (ref "U4") (pin "4") (pinfunction "nFAULT_4") (pintype "passive"))
    )
    (net (code "59") (name "Net-(U4-nSLEEP)") (class "Default")
      (node (ref "R9") (pin "2") (pinfunction "2_2") (pintype "passive"))
      (node (ref "U4") (pin "3") (pinfunction "nSLEEP_3") (pintype "passive"))
    )
    (net (code "60") (name "Net-(U5-CPH)") (class "Default")
      (node (ref "C23") (pin "2") (pinfunction "2_2") (pintype "passive"))
      (node (ref "U5") (pin "13") (pinfunction "CPH_13") (pintype "passive"))
    )
    (net (code "61") (name "Net-(U5-CPL)") (class "Default")
      (node (ref "C23") (pin "1") (pinfunction "1_1") (pintype "passive"))
      (node (ref "U5") (pin "14") (pinfunction "CPL_14") (pintype "passive"))
    )
    (net (code "62") (name "Net-(U5-IPROPI)") (class "Default")
      (node (ref "R17") (pin "2") (pinfunction "2_2") (pintype "passive"))
      (node (ref "U5") (pin "6") (pinfunction "IPROPI_6") (pintype "passive"))
    )
    (net (code "63") (name "Net-(U5-OUT1)") (class "Default")
      (node (ref "J6") (pin "1") (pinfunction "1_1") (pintype "passive"))
      (node (ref "U5") (pin "8") (pinfunction "OUT1_8") (pintype "passive"))
    )
    (net (code "64") (name "Net-(U5-OUT2)") (class "Default")
      (node (ref "J7") (pin "1") (pinfunction "1_1") (pintype "passive"))
      (node (ref "U5") (pin "10") (pinfunction "OUT2_10") (pintype "passive"))
    )
    (net (code "65") (name "Net-(U5-VCP)") (class "Default")
      (node (ref "C22") (pin "1") (pinfunction "1_1") (pintype "passive"))
      (node (ref "U5") (pin "12") (pinfunction "VCP_12") (pintype "passive"))
    )
    (net (code "66") (name "Net-(U5-nFAULT)") (class "Default")
      (node (ref "R15") (pin "2") (pinfunction "2_2") (pintype "passive"))
      (node (ref "U5") (pin "4") (pinfunction "nFAULT_4") (pintype "passive"))
    )
    (net (code "67") (name "Net-(U5-nSLEEP)") (class "Default")
      (node (ref "R14") (pin "2") (pinfunction "2_2") (pintype "passive"))
      (node (ref "U5") (pin "3") (pinfunction "nSLEEP_3") (pintype "passive"))
    )
    (net (code "68") (name "VCC(12v)") (class "Default")
      (node (ref "C12") (pin "2") (pinfunction "2_2") (pintype "passive"))
      (node (ref "C13") (pin "1") (pinfunction "1_1") (pintype "passive"))
      (node (ref "C14") (pin "2") (pinfunction "2_2") (pintype "passive"))
      (node (ref "C15") (pin "2") (pinfunction "2_2") (pintype "passive"))
      (node (ref "C16") (pin "1") (pinfunction "1_1") (pintype "passive"))
      (node (ref "C17") (pin "2") (pinfunction "2_2") (pintype "passive"))
      (node (ref "C20") (pin "2") (pinfunction "2_2") (pintype "passive"))
      (node (ref "C21") (pin "1") (pinfunction "1_1") (pintype "passive"))
      (node (ref "C22") (pin "2") (pinfunction "2_2") (pintype "passive"))
      (node (ref "U3") (pin "11") (pinfunction "VM_11") (pintype "passive"))
      (node (ref "U4") (pin "11") (pinfunction "VM_11") (pintype "passive"))
      (node (ref "U5") (pin "11") (pinfunction "VM_11") (pintype "passive"))
    )
    (net (code "69") (name "VCC(MB)") (class "Default")
      (node (ref "C5") (pin "1") (pinfunction "1_1") (pintype "passive"))
      (node (ref "C6") (pin "1") (pinfunction "1_1") (pintype "passive"))
      (node (ref "C7") (pin "2") (pinfunction "2_2") (pintype "passive"))
      (node (ref "Q1") (pin "3") (pinfunction "S_3") (pintype "passive"))
      (node (ref "R2") (pin "2") (pinfunction "2_2") (pintype "passive"))
      (node (ref "U2") (pin "1") (pinfunction "IN_1") (pintype "passive"))
      (node (ref "ZD1") (pin "1") (pinfunction "K_1") (pintype "passive"))
    )
    (net (code "70") (name "unconnected-(J8-RX-Pad7)") (class "Default")
      (node (ref "J8") (pin "7") (pinfunction "RX_7") (pintype "passive"))
    )
    (net (code "71") (name "unconnected-(J8-SWO-Pad6)") (class "Default")
      (node (ref "J8") (pin "6") (pinfunction "SWO_6") (pintype "passive"))
    )
    (net (code "72") (name "unconnected-(J8-TDI-Pad8)") (class "Default")
      (node (ref "J8") (pin "8") (pinfunction "TDI_8") (pintype "passive"))
    )
    (net (code "73") (name "unconnected-(U1-NC-Pad4)") (class "Default")
      (node (ref "U1") (pin "4") (pinfunction "NC_4") (pintype "passive"))
    )
    (net (code "74") (name "unconnected-(U2-NC-Pad4)") (class "Default")
      (node (ref "U2") (pin "4") (pinfunction "NC_4") (pintype "passive"))
    )
    (net (code "75") (name "unconnected-(U6-PA7-Pad12)") (class "Default")
      (node (ref "U6") (pin "12") (pinfunction "PA7_12") (pintype "passive"))
    )
    (net (code "76") (name "unconnected-(U6-PA15-Pad25)") (class "Default")
      (node (ref "U6") (pin "25") (pinfunction "PA15_25") (pintype "passive"))
    )
    (net (code "77") (name "unconnected-(U6-PBO-Pad13)") (class "Default")
      (node (ref "U6") (pin "13") (pinfunction "PBO_13") (pintype "passive"))
    )
    (net (code "78") (name "unconnected-(U6-PF0-OSC_IN-Pad2)") (class "Default")
      (node (ref "U6") (pin "2") (pinfunction "PF0-OSC_IN_2") (pintype "passive"))
    )
    (net (code "79") (name "unconnected-(U6-PF1-OSC_OUT-Pad3)") (class "Default")
      (node (ref "U6") (pin "3") (pinfunction "PF1-OSC_OUT_3") (pintype "passive"))
    )
    (net (code "80") (name "unconnected-(U11-Pad3)") (class "Default")
      (node (ref "U11") (pin "3") (pinfunction "3_3") (pintype "passive"))
    )
    (net (code "81") (name "unconnected-(U11-Pad4)") (class "Default")
      (node (ref "U11") (pin "4") (pinfunction "4_4") (pintype "passive"))
    )
    (net (code "82") (name "unconnected-(USB1-ID-Pad4)") (class "Default")
      (node (ref "USB1") (pin "4") (pinfunction "ID_4") (pintype "passive"))
    )
    (net (code "83") (name "unconnected-(USB1-S-Pad6)") (class "Default")
      (node (ref "USB1") (pin "6") (pinfunction "S_6") (pintype "passive"))
    )
  )
)
